# Trinamic_Driver_Schematic.net
KiCad netlist of a schematic drawn in Altium Designer
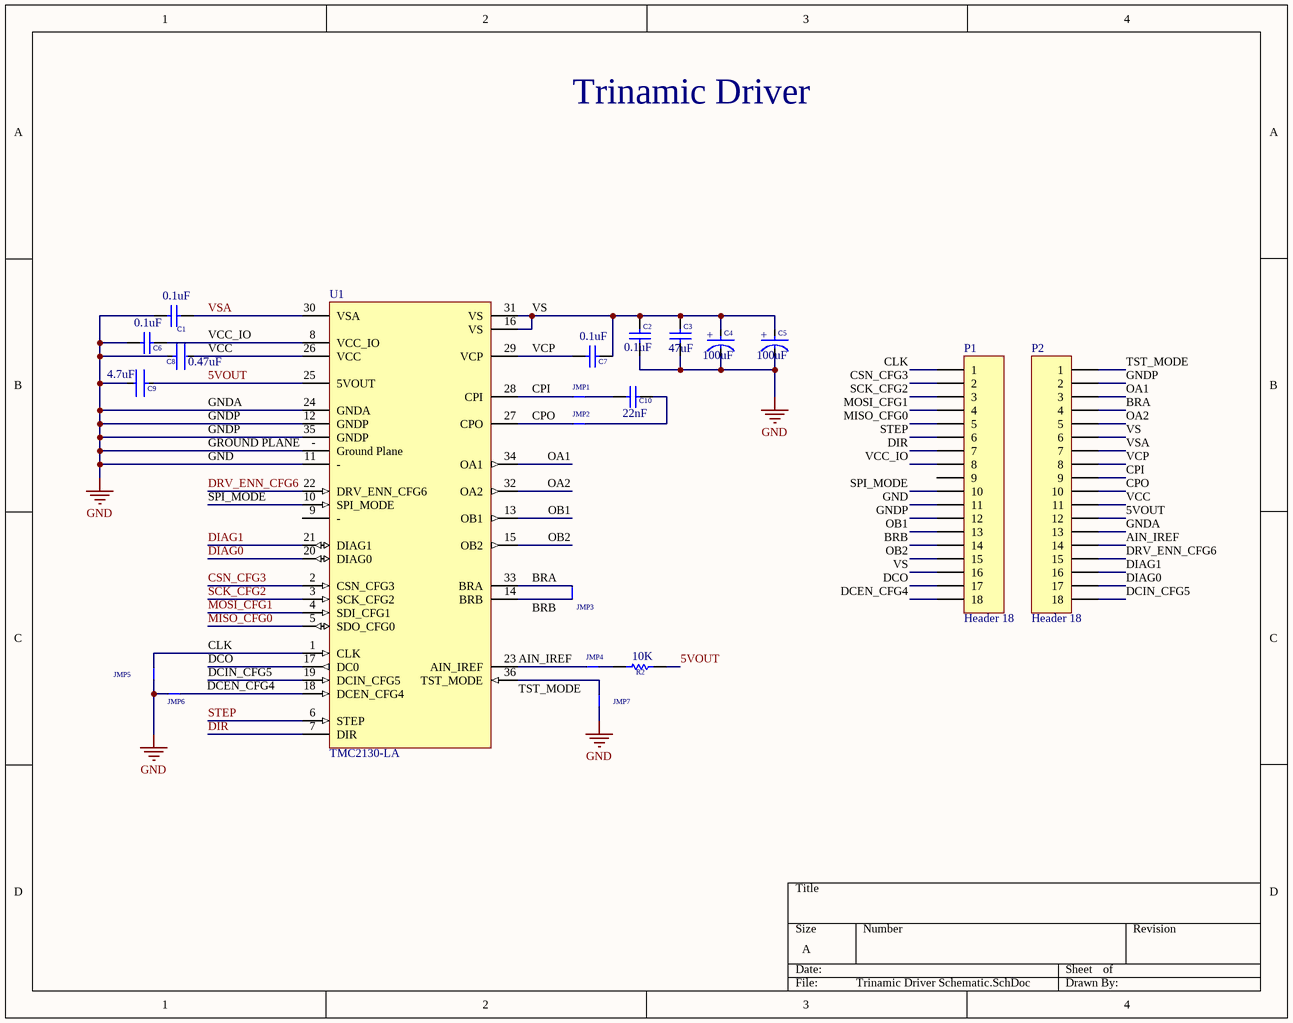
[diagram p0: Trinamic Driver Schematic.SchDoc]

(export (version "E")
  (design (tool "Eeschema 10.0.6"))
  (components
    (comp (ref "C1")
      (value "0.1uF")
      (footprint "CAPC1608X90X20LL10")
      (description "Chip Capacitor, 0.1 uF, +/- 10%, 50 V, -55 to 125 degC, 0603 (1608 Metric), RoHS, Tape and Reel")
      (fields (field (name "VOLTAGE") "50V") (field (name "TOLERANCE") "10%"))
      (libsource (lib "Altium Content Vault") (part "CAP-NP-2"))
    )
    (comp (ref "C2")
      (value "0.1uF")
      (footprint "CAPC1608X90X20LL10")
      (description "Chip Capacitor, 0.1 uF, +/- 10%, 50 V, -55 to 125 degC, 0603 (1608 Metric), RoHS, Tape and Reel")
      (fields (field (name "VOLTAGE") "50V") (field (name "TOLERANCE") "10%"))
      (libsource (lib "Altium Content Vault") (part "CAP-NP-2"))
    )
    (comp (ref "C3")
      (value "47uF")
      (footprint "CAPC3225X270X50LL20T25")
      (description "Chip Capacitor, 47 uF, +/- 20%, 16 V, -55 to 85 degC, 1210 (3225 Metric), RoHS, Tape and Reel")
      (fields (field (name "TOLERANCE") "±20%") (field (name "MANUFACTURER") "Kemet"))
      (libsource (lib "Altium Content Vault") (part "CAP-NP-2"))
    )
    (comp (ref "C4")
      (value "100uF")
      (footprint "FP-EEE-FK1H101P-MFG")
      (description "CAP ALUM 100UF 20% 50V SMD")
      (fields (field (name "TOLERANCE") "20%") (field (name "MANUFACTURER PART NUMBER") "EEE-FK1H101P"))
      (libsource (lib "Altium Content Vault") (part "cf48714ba7e38822c1575c7ec0b6d1f"))
    )
    (comp (ref "C5")
      (value "100uF")
      (footprint "FP-EEE-FK1H101P-MFG")
      (description "CAP ALUM 100UF 20% 50V SMD")
      (fields (field (name "TOLERANCE") "20%") (field (name "MANUFACTURER PART NUMBER") "EEE-FK1H101P"))
      (libsource (lib "Altium Content Vault") (part "cf48714ba7e38822c1575c7ec0b6d1f"))
    )
    (comp (ref "C6")
      (value "0.1uF")
      (footprint "CAPC1608X90X20LL10")
      (description "Chip Capacitor, 0.1 uF, +/- 10%, 50 V, -55 to 125 degC, 0603 (1608 Metric), RoHS, Tape and Reel")
      (fields (field (name "VOLTAGE") "50V") (field (name "TOLERANCE") "10%"))
      (libsource (lib "Altium Content Vault") (part "CAP-NP-2"))
    )
    (comp (ref "C7")
      (value "0.1uF")
      (footprint "CAPC1608X90X20LL10")
      (description "Chip Capacitor, 0.1 uF, +/- 10%, 50 V, -55 to 125 degC, 0603 (1608 Metric), RoHS, Tape and Reel")
      (fields (field (name "VOLTAGE") "50V") (field (name "TOLERANCE") "10%"))
      (libsource (lib "Altium Content Vault") (part "CAP-NP-2"))
    )
    (comp (ref "C8")
      (value "0.47uF")
      (footprint "FP-C0603C-CF-MFG")
      (description "CAP CER 0.47UF 16V X7R 0603")
      (fields (field (name "TOLERANCE") "0.1") (field (name "MANUFACTURER PART NUMBER") "C0603C474K4RACTU"))
      (libsource (lib "Altium Content Vault") (part "b4654b650e69147ec39a6b967a45e02"))
    )
    (comp (ref "C9")
      (value "4.7uF")
      (footprint "FP-C0603-CG-MFG")
      (description "CAP CER 4.7UF 6.3V X5R 0603")
      (fields (field (name "TOLERANCE") "10%") (field (name "MANUFACTURER") "Kemet"))
      (libsource (lib "Altium Content Vault") (part "11868f565c42a9108669ba33697ecf6"))
    )
    (comp (ref "C10")
      (value "22nF")
      (footprint "CAPC1608X90X40ML10T20")
      (description "Chip Capacitor, 22 nF, +/- 10%, 50 V, -55 to 125 degC, 0603 (1608 Metric), RoHS, Tape and Reel")
      (fields (field (name "MANUFACTURER") "Yageo") (field (name "TOLERANCE") "10%"))
      (libsource (lib "Altium Content Vault") (part "CAP-NP-2"))
    )
    (comp (ref "JMP1")
      (value "Solder Jump")
      (footprint "Solder Jump")
      (libsource (lib "SDP21_Symbols") (part "Solder Jump"))
    )
    (comp (ref "JMP2")
      (value "Solder Jump")
      (footprint "Solder Jump")
      (libsource (lib "SDP21_Symbols") (part "Solder Jump"))
    )
    (comp (ref "JMP3")
      (value "Solder Jump")
      (footprint "Solder Jump")
      (libsource (lib "SDP21_Symbols") (part "Solder Jump"))
    )
    (comp (ref "JMP4")
      (value "Solder Jump")
      (footprint "Solder Jump")
      (libsource (lib "SDP21_Symbols") (part "Solder Jump"))
    )
    (comp (ref "JMP5")
      (value "Solder Jump")
      (footprint "Solder Jump")
      (libsource (lib "SDP21_Symbols") (part "Solder Jump"))
    )
    (comp (ref "JMP6")
      (value "Solder Jump")
      (footprint "Solder Jump")
      (libsource (lib "SDP21_Symbols") (part "Solder Jump"))
    )
    (comp (ref "JMP7")
      (value "Solder Jump")
      (footprint "Solder Jump")
      (libsource (lib "SDP21_Symbols") (part "Solder Jump"))
    )
    (comp (ref "P1")
      (value "Header 18")
      (footprint "HDR1X18")
      (description "Header, 18-Pin")
      (fields (field (name "PUBLISHER") "Altium Limited"))
      (libsource (lib "Miscellaneous Connectors") (part "Header 18"))
    )
    (comp (ref "P2")
      (value "Header 18")
      (footprint "HDR1X18")
      (description "Header, 18-Pin")
      (fields (field (name "PUBLISHER") "Altium Limited"))
      (libsource (lib "") (part "Header 18_1"))
    )
    (comp (ref "R2")
      (value "10K")
      (footprint "RESC1609X55X30LL15T15")
      (description "Chip Resistor, 10 KOhm, +/- 1%, 0.1 W, -55 to 155 degC, 0603 (1608 Metric), RoHS, Tape and Reel")
      (fields (field (name "TOLERANCE") "1%") (field (name "MANUFACTURER") "Panasonic"))
      (libsource (lib "Altium Content Vault") (part "RES-2"))
    )
    (comp (ref "U1")
      (value "TMC2130-LA")
      (footprint "QFN-36")
      (description "TMC2130-LA Trinamic Driver QFN-36")
      (libsource (lib "SDP21_Symbols") (part "TMC2130-LA"))
    )
  )
  (nets
    (net (code "1") (name "/5VOUT") (class "Default")
      (node (ref "C9") (pin "1") (pinfunction "1_1") (pintype "passive"))
      (node (ref "P2") (pin "12") (pinfunction "12_12") (pintype "passive"))
      (node (ref "R2") (pin "2") (pinfunction "2_2") (pintype "passive"))
      (node (ref "U1") (pin "25") (pinfunction "5VOUT_25") (pintype "power_in"))
    )
    (net (code "2") (name "/AIN_IREF") (class "Default")
      (node (ref "JMP4") (pin "1") (pinfunction "1_1") (pintype "passive"))
      (node (ref "P2") (pin "14") (pinfunction "14_14") (pintype "passive"))
      (node (ref "U1") (pin "23") (pinfunction "AIN_IREF_23") (pintype "passive"))
    )
    (net (code "3") (name "/BRA") (class "Default")
      (node (ref "JMP3") (pin "2") (pinfunction "2_2") (pintype "passive"))
      (node (ref "P2") (pin "4") (pinfunction "4_4") (pintype "passive"))
      (node (ref "U1") (pin "33") (pinfunction "BRA_33") (pintype "passive"))
    )
    (net (code "4") (name "/BRB") (class "Default")
      (node (ref "JMP3") (pin "1") (pinfunction "1_1") (pintype "passive"))
      (node (ref "P1") (pin "14") (pinfunction "14_14") (pintype "passive"))
      (node (ref "U1") (pin "14") (pinfunction "BRB_14") (pintype "passive"))
    )
    (net (code "5") (name "/CLK") (class "Default")
      (node (ref "JMP5") (pin "2") (pinfunction "2_2") (pintype "passive"))
      (node (ref "P1") (pin "1") (pinfunction "1_1") (pintype "passive"))
      (node (ref "U1") (pin "1") (pinfunction "CLK_1") (pintype "input"))
    )
    (net (code "6") (name "/CPI") (class "Default")
      (node (ref "JMP1") (pin "1") (pinfunction "1_1") (pintype "passive"))
      (node (ref "P2") (pin "9") (pinfunction "9_9") (pintype "passive"))
      (node (ref "U1") (pin "28") (pinfunction "CPI_28") (pintype "passive"))
    )
    (net (code "7") (name "/CPO") (class "Default")
      (node (ref "JMP2") (pin "1") (pinfunction "1_1") (pintype "passive"))
      (node (ref "P2") (pin "10") (pinfunction "10_10") (pintype "passive"))
      (node (ref "U1") (pin "27") (pinfunction "CPO_27") (pintype "passive"))
    )
    (net (code "8") (name "/CSN_CFG3") (class "Default")
      (node (ref "P1") (pin "2") (pinfunction "2_2") (pintype "passive"))
      (node (ref "U1") (pin "2") (pinfunction "CSN_CFG3_2") (pintype "input"))
    )
    (net (code "9") (name "/DCEN_CFG4") (class "Default")
      (node (ref "JMP6") (pin "1") (pinfunction "1_1") (pintype "passive"))
      (node (ref "P1") (pin "18") (pinfunction "18_18") (pintype "passive"))
      (node (ref "U1") (pin "18") (pinfunction "DCEN_CFG4_18") (pintype "input"))
    )
    (net (code "10") (name "/DCIN_CFG5") (class "Default")
      (node (ref "P2") (pin "18") (pinfunction "18_18") (pintype "passive"))
      (node (ref "U1") (pin "19") (pinfunction "DCIN_CFG5_19") (pintype "input"))
    )
    (net (code "11") (name "/DCO") (class "Default")
      (node (ref "P1") (pin "17") (pinfunction "17_17") (pintype "passive"))
      (node (ref "U1") (pin "17") (pinfunction "DC0_17") (pintype "output"))
    )
    (net (code "12") (name "/DIAG0") (class "Default")
      (node (ref "P2") (pin "17") (pinfunction "17_17") (pintype "passive"))
      (node (ref "U1") (pin "20") (pinfunction "DIAG0_20") (pintype "bidirectional"))
    )
    (net (code "13") (name "/DIAG1") (class "Default")
      (node (ref "P2") (pin "16") (pinfunction "16_16") (pintype "passive"))
      (node (ref "U1") (pin "21") (pinfunction "DIAG1_21") (pintype "bidirectional"))
    )
    (net (code "14") (name "/DIR") (class "Default")
      (node (ref "P1") (pin "7") (pinfunction "7_7") (pintype "passive"))
      (node (ref "U1") (pin "7") (pinfunction "DIR_7") (pintype "passive"))
    )
    (net (code "15") (name "/DRV_ENN_CFG6") (class "Default")
      (node (ref "P2") (pin "15") (pinfunction "15_15") (pintype "passive"))
      (node (ref "U1") (pin "22") (pinfunction "DRV_ENN_CFG6_22") (pintype "input"))
    )
    (net (code "16") (name "/MISO_CFG0") (class "Default")
      (node (ref "P1") (pin "5") (pinfunction "5_5") (pintype "passive"))
      (node (ref "U1") (pin "5") (pinfunction "SDO_CFG0_5") (pintype "bidirectional"))
    )
    (net (code "17") (name "/MOSI_CFG1") (class "Default")
      (node (ref "P1") (pin "4") (pinfunction "4_4") (pintype "passive"))
      (node (ref "U1") (pin "4") (pinfunction "SDI_CFG1_4") (pintype "input"))
    )
    (net (code "18") (name "/OA1") (class "Default")
      (node (ref "P2") (pin "3") (pinfunction "3_3") (pintype "passive"))
      (node (ref "U1") (pin "34") (pinfunction "OA1_34") (pintype "output"))
    )
    (net (code "19") (name "/OA2") (class "Default")
      (node (ref "P2") (pin "5") (pinfunction "5_5") (pintype "passive"))
      (node (ref "U1") (pin "32") (pinfunction "OA2_32") (pintype "output"))
    )
    (net (code "20") (name "/OB1") (class "Default")
      (node (ref "P1") (pin "13") (pinfunction "13_13") (pintype "passive"))
      (node (ref "U1") (pin "13") (pinfunction "OB1_13") (pintype "output"))
    )
    (net (code "21") (name "/OB2") (class "Default")
      (node (ref "P1") (pin "15") (pinfunction "15_15") (pintype "passive"))
      (node (ref "U1") (pin "15") (pinfunction "OB2_15") (pintype "output"))
    )
    (net (code "22") (name "/SCK_CFG2") (class "Default")
      (node (ref "P1") (pin "3") (pinfunction "3_3") (pintype "passive"))
      (node (ref "U1") (pin "3") (pinfunction "SCK_CFG2_3") (pintype "input"))
    )
    (net (code "23") (name "/SPI_MODE") (class "Default")
      (node (ref "P1") (pin "10") (pinfunction "10_10") (pintype "passive"))
      (node (ref "U1") (pin "10") (pinfunction "SPI_MODE_10") (pintype "input"))
    )
    (net (code "24") (name "/STEP") (class "Default")
      (node (ref "P1") (pin "6") (pinfunction "6_6") (pintype "passive"))
      (node (ref "U1") (pin "6") (pinfunction "STEP_6") (pintype "input"))
    )
    (net (code "25") (name "/TST_MODE") (class "Default")
      (node (ref "JMP7") (pin "1") (pinfunction "1_1") (pintype "passive"))
      (node (ref "P2") (pin "1") (pinfunction "1_1") (pintype "passive"))
      (node (ref "U1") (pin "36") (pinfunction "TST_MODE_36") (pintype "input"))
    )
    (net (code "26") (name "/VCC") (class "Default")
      (node (ref "C8") (pin "2") (pinfunction "2_2") (pintype "passive"))
      (node (ref "P2") (pin "11") (pinfunction "11_11") (pintype "passive"))
      (node (ref "U1") (pin "26") (pinfunction "VCC_26") (pintype "power_in"))
    )
    (net (code "27") (name "/VCC_IO") (class "Default")
      (node (ref "C6") (pin "2") (pinfunction "2_2") (pintype "passive"))
      (node (ref "P1") (pin "8") (pinfunction "8_8") (pintype "passive"))
      (node (ref "U1") (pin "8") (pinfunction "VCC_IO_8") (pintype "power_in"))
    )
    (net (code "28") (name "/VCP") (class "Default")
      (node (ref "C7") (pin "2") (pinfunction "2_2") (pintype "passive"))
      (node (ref "P2") (pin "8") (pinfunction "8_8") (pintype "passive"))
      (node (ref "U1") (pin "29") (pinfunction "VCP_29") (pintype "passive"))
    )
    (net (code "29") (name "/VS") (class "Default")
      (node (ref "C2") (pin "2") (pinfunction "2_2") (pintype "passive"))
      (node (ref "C3") (pin "2") (pinfunction "2_2") (pintype "passive"))
      (node (ref "C4") (pin "2") (pinfunction "A_2") (pintype "passive"))
      (node (ref "C5") (pin "2") (pinfunction "A_2") (pintype "passive"))
      (node (ref "C7") (pin "1") (pinfunction "1_1") (pintype "passive"))
      (node (ref "P1") (pin "16") (pinfunction "16_16") (pintype "passive"))
      (node (ref "P2") (pin "6") (pinfunction "6_6") (pintype "passive"))
      (node (ref "U1") (pin "16") (pinfunction "VS_16") (pintype "power_in"))
      (node (ref "U1") (pin "31") (pinfunction "VS_31") (pintype "power_in"))
    )
    (net (code "30") (name "/VSA") (class "Default")
      (node (ref "C1") (pin "2") (pinfunction "2_2") (pintype "passive"))
      (node (ref "P2") (pin "7") (pinfunction "7_7") (pintype "passive"))
      (node (ref "U1") (pin "30") (pinfunction "VSA_30") (pintype "power_in"))
    )
    (net (code "31") (name "GND") (class "Default")
      (node (ref "C1") (pin "1") (pinfunction "1_1") (pintype "passive"))
      (node (ref "C2") (pin "1") (pinfunction "1_1") (pintype "passive"))
      (node (ref "C3") (pin "1") (pinfunction "1_1") (pintype "passive"))
      (node (ref "C4") (pin "1") (pinfunction "C_1") (pintype "passive"))
      (node (ref "C5") (pin "1") (pinfunction "C_1") (pintype "passive"))
      (node (ref "C6") (pin "1") (pinfunction "1_1") (pintype "passive"))
      (node (ref "C8") (pin "1") (pinfunction "1_1") (pintype "passive"))
      (node (ref "C9") (pin "2") (pinfunction "2_2") (pintype "passive"))
      (node (ref "JMP5") (pin "1") (pinfunction "1_1") (pintype "passive"))
      (node (ref "JMP6") (pin "2") (pinfunction "2_2") (pintype "passive"))
      (node (ref "JMP7") (pin "2") (pinfunction "2_2") (pintype "passive"))
      (node (ref "P1") (pin "11") (pinfunction "11_11") (pintype "passive"))
      (node (ref "P1") (pin "12") (pinfunction "12_12") (pintype "passive"))
      (node (ref "P2") (pin "13") (pinfunction "13_13") (pintype "passive"))
      (node (ref "P2") (pin "2") (pinfunction "2_2") (pintype "passive"))
      (node (ref "U1") (pin "-") (pinfunction "Ground_Plane_-") (pintype "passive"))
      (node (ref "U1") (pin "11") (pinfunction "-_11") (pintype "passive"))
      (node (ref "U1") (pin "12") (pinfunction "GNDP_12") (pintype "power_in"))
      (node (ref "U1") (pin "24") (pinfunction "GNDA_24") (pintype "power_in"))
      (node (ref "U1") (pin "35") (pinfunction "GNDP_35") (pintype "power_in"))
    )
    (net (code "32") (name "Net-(C10-Pad1)") (class "Default")
      (node (ref "C10") (pin "1") (pinfunction "1_1") (pintype "passive"))
      (node (ref "JMP1") (pin "2") (pinfunction "2_2") (pintype "passive"))
    )
    (net (code "33") (name "Net-(C10-Pad2)") (class "Default")
      (node (ref "C10") (pin "2") (pinfunction "2_2") (pintype "passive"))
      (node (ref "JMP2") (pin "2") (pinfunction "2_2") (pintype "passive"))
    )
    (net (code "34") (name "Net-(JMP4-Pad2)") (class "Default")
      (node (ref "JMP4") (pin "2") (pinfunction "2_2") (pintype "passive"))
      (node (ref "R2") (pin "1") (pinfunction "1_1") (pintype "passive"))
    )
    (net (code "35") (name "unconnected-(P1-Pad9)") (class "Default")
      (node (ref "P1") (pin "9") (pinfunction "9_9") (pintype "passive"))
    )
    (net (code "36") (name "unconnected-(U1---Pad9)") (class "Default")
      (node (ref "U1") (pin "9") (pinfunction "-_9") (pintype "tri_state"))
    )
  )
)
